# Power_-_5V0.net
KiCad netlist of a schematic drawn in Altium Designer
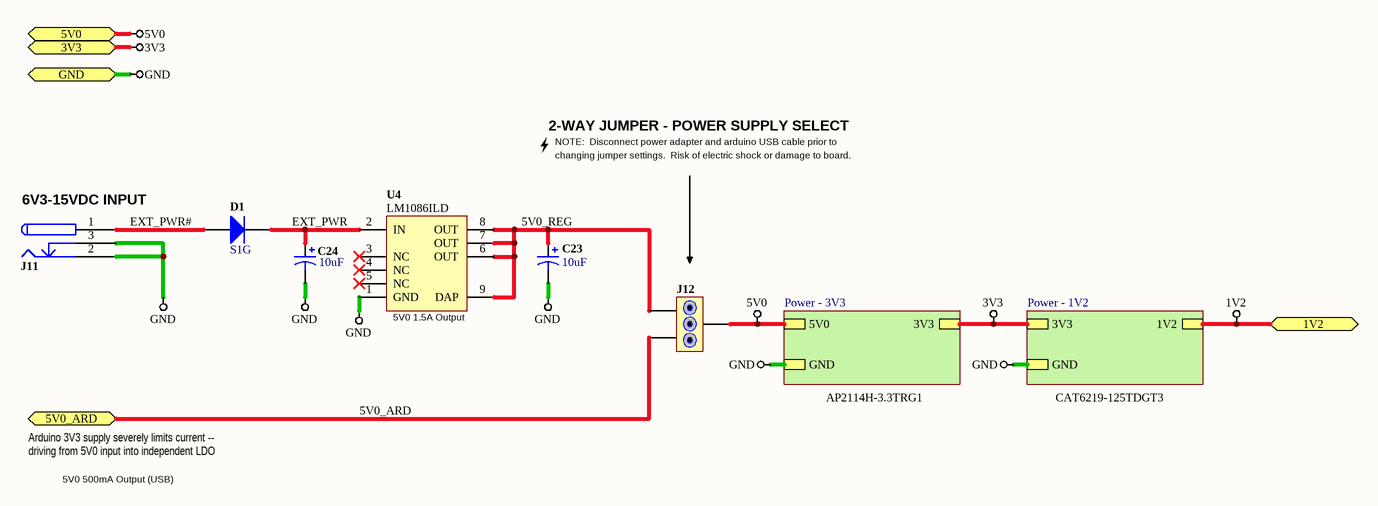
[diagram p0: Power - 5V0.SchDoc]

(export (version "E")
  (design (tool "Eeschema 10.0.6"))
  (components
    (comp (ref "C23")
      (value "TAJB106K020R")
      (footprint "AVX-CAPC3528_V")
      (description "Capacitor, Tantalum, 10uF 10% 20V MCCT-B (3528)")
      (fields
        (field (name "CAPACITANCE") "10uF")
        (field (name "MANUFACTURER") "AVX")
        (field (name "TOLERANCE") "10%")
      )
      (libsource (lib "Altium Content Vault") (part "CMP-0279-00001-1"))
    )
    (comp (ref "C24")
      (value "TAJB106K020R")
      (footprint "AVX-CAPC3528_V")
      (description "Capacitor, Tantalum, 10uF 10% 20V MCCT-B (3528)")
      (fields
        (field (name "CAPACITANCE") "10uF")
        (field (name "MANUFACTURER") "AVX")
        (field (name "TOLERANCE") "10%")
      )
      (libsource (lib "Altium Content Vault") (part "CMP-0279-00001-1"))
    )
    (comp (ref "D1")
      (value "S1G")
      (footprint "DO-214AC")
      (description "Fairchild S1G General Purpose Rectifier")
      (libsource (lib "DIODE-S1G") (part "S1G"))
    )
    (comp (ref "J11")
      (value "PWR CONNECTOR")
      (footprint "PJ-102AH")
      (description "Connector, 3 Conductor Power Jack")
      (fields (field (name "MANUFACTURER PART NUMBER") "CP-102AH-ND"))
      (libsource (lib "PWR_CONNECTOR_3") (part "POWER-CONNECTOR-3"))
    )
    (comp (ref "J12")
      (value "3-WAY JUMPER")
      (footprint "HDR1X3")
      (description "3-Way Jumper - Center Output")
      (fields (field (name "MANUFACTURER PART NUMBER") "71417-103HLF"))
      (libsource (lib "3-WAY JUMPER") (part "3-WAY JUMPER"))
    )
    (comp (ref "U4")
      (value "LM1086ILD-3.3/NOPB")
      (footprint "LDC08A")
      (description "1.5A Low Dropout Positive Regulators, 8-pin LLP, Pb-Free")
      (fields
        (field (name "MANUFACTURER") "National Semiconductor")
        (field (name "ABBREVIATED NAME") "LM1086ILD")
      )
      (libsource (lib "Altium Content Vault") (part "CMP-0062-01489-2"))
    )
  )
  (nets
    (net (code "1") (name "/5V0_ARD") (class "Default")
      (node (ref "J12") (pin "3") (pinfunction "3_3") (pintype "passive"))
    )
    (net (code "2") (name "/5V0_REG") (class "Default")
      (node (ref "C23") (pin "1") (pinfunction "1_1") (pintype "passive"))
      (node (ref "J12") (pin "1") (pinfunction "1_1") (pintype "passive"))
      (node (ref "U4") (pin "6") (pinfunction "OUT_6") (pintype "power_in"))
      (node (ref "U4") (pin "7") (pinfunction "OUT_7") (pintype "power_in"))
      (node (ref "U4") (pin "8") (pinfunction "OUT_8") (pintype "power_in"))
      (node (ref "U4") (pin "9") (pinfunction "DAP_9") (pintype "power_in"))
    )
    (net (code "3") (name "/EXT_PWR") (class "Default")
      (node (ref "C24") (pin "1") (pinfunction "1_1") (pintype "passive"))
      (node (ref "D1") (pin "2") (pinfunction "2_2") (pintype "passive"))
      (node (ref "U4") (pin "2") (pinfunction "IN_2") (pintype "power_in"))
    )
    (net (code "4") (name "/EXT_PWR#") (class "Default")
      (node (ref "D1") (pin "1") (pinfunction "1_1") (pintype "passive"))
      (node (ref "J11") (pin "1") (pintype "power_in"))
    )
    (net (code "7") (name "5V0") (class "Default")
      (node (ref "J12") (pin "2") (pinfunction "2_2") (pintype "passive"))
    )
    (net (code "8") (name "GND") (class "Default")
      (node (ref "C23") (pin "2") (pinfunction "2_2") (pintype "passive"))
      (node (ref "C24") (pin "2") (pinfunction "2_2") (pintype "passive"))
      (node (ref "J11") (pin "2") (pintype "power_in"))
      (node (ref "J11") (pin "3") (pintype "power_in"))
      (node (ref "U4") (pin "1") (pinfunction "GND_1") (pintype "power_in"))
    )
    (net (code "9") (name "unconnected-(U4-NC-Pad3)") (class "Default")
      (node (ref "U4") (pin "3") (pinfunction "NC_3") (pintype "passive+no_connect"))
    )
    (net (code "10") (name "unconnected-(U4-NC-Pad4)") (class "Default")
      (node (ref "U4") (pin "4") (pinfunction "NC_4") (pintype "passive+no_connect"))
    )
    (net (code "11") (name "unconnected-(U4-NC-Pad5)") (class "Default")
      (node (ref "U4") (pin "5") (pinfunction "NC_5") (pintype "passive+no_connect"))
    )
  )
)
